# Seaquencer.net
KiCad netlist of a schematic drawn in EAGLE
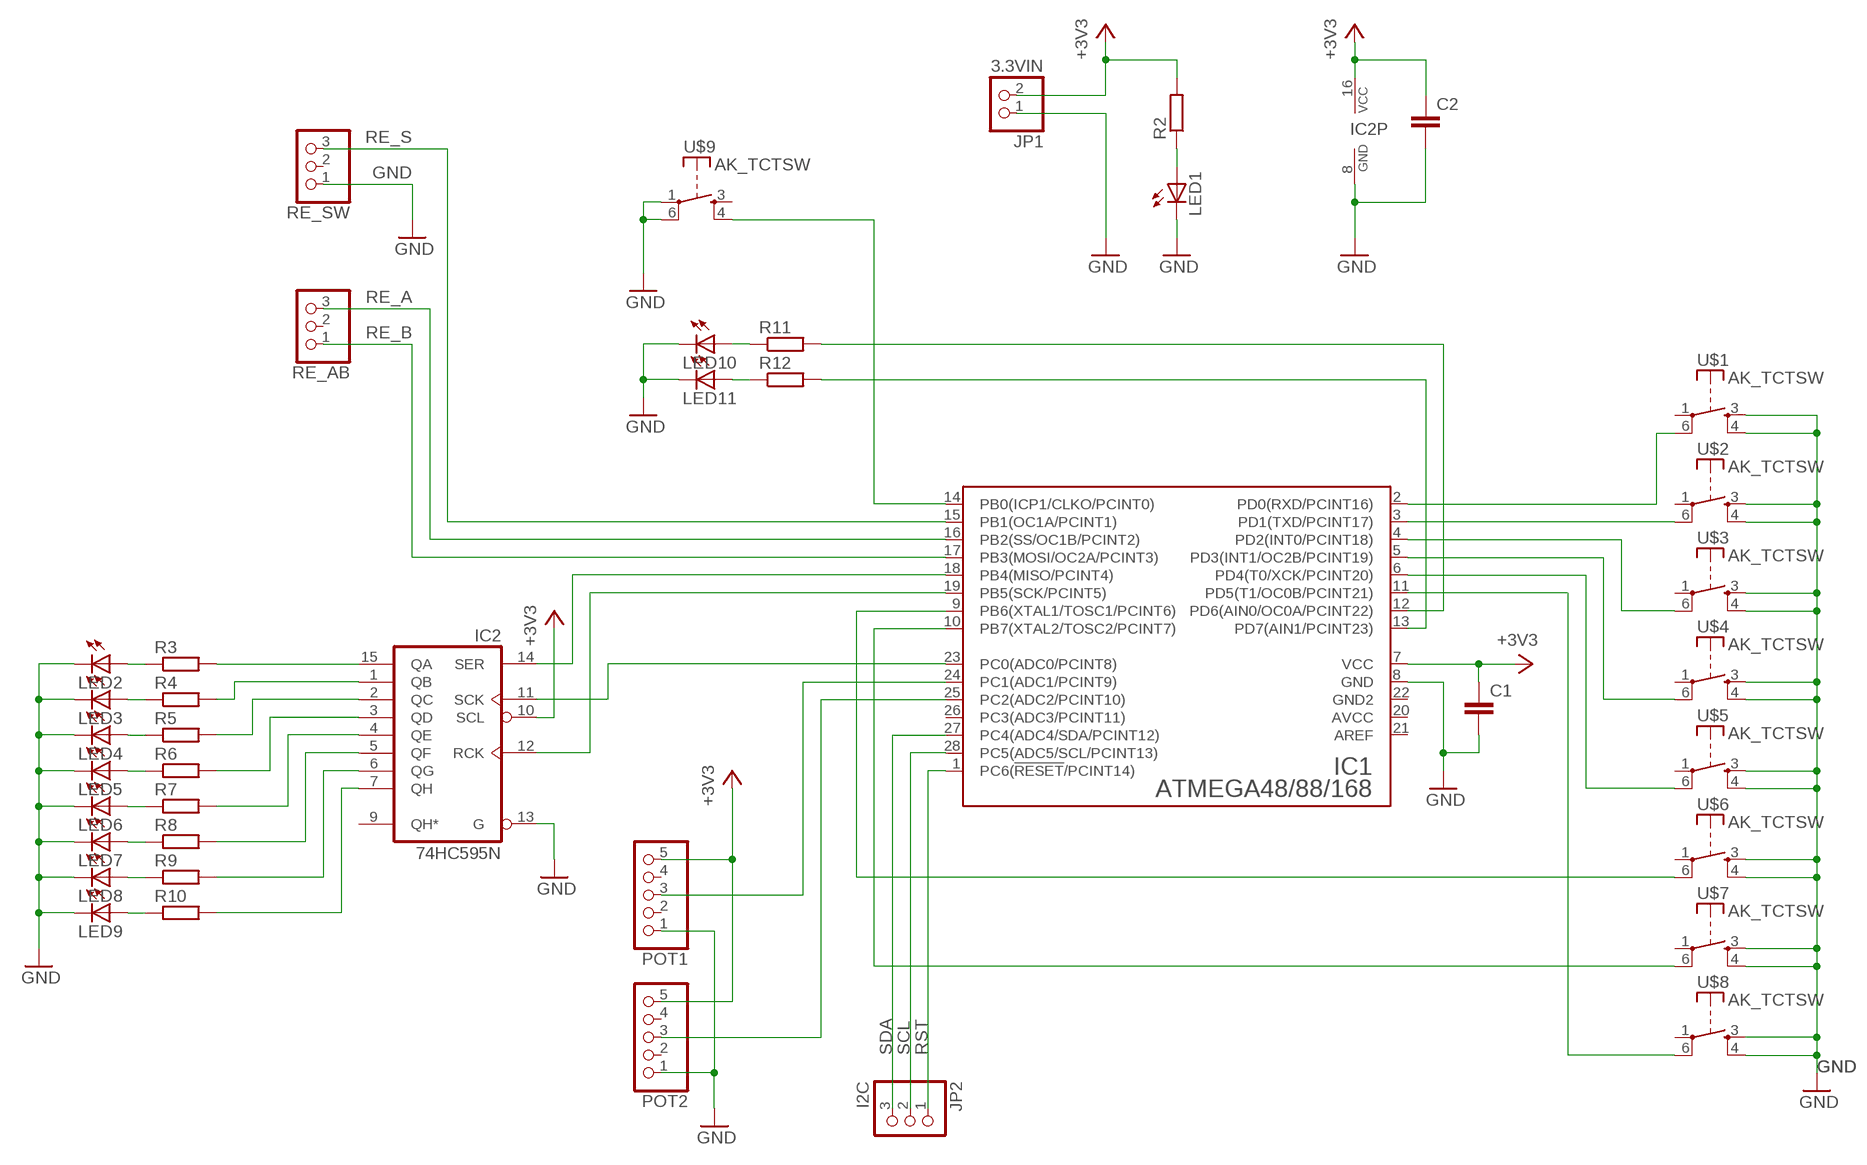
[diagram p0: schematic, sheet 1]

(export (version "E")
  (design (tool "Eeschema 10.0.6"))
  (components
    (comp (ref "C1")
      (value "C-EU025-024X044")
      (footprint "eagle-import:C025-024X044")
      (libsource (lib "eagle-import") (part "C-EU025-024X044"))
    )
    (comp (ref "C2")
      (value "C-EU025-024X044")
      (footprint "eagle-import:C025-024X044")
      (libsource (lib "eagle-import") (part "C-EU025-024X044"))
    )
    (comp (ref "IC1")
      (value "ATMEGA48/88/168")
      (footprint "eagle-import:DIL28-3")
      (libsource (lib "eagle-import") (part "ATMEGA48/88/168"))
    )
    (comp (ref "IC2")
      (value "74HC595N")
      (footprint "eagle-import:DIL16")
      (libsource (lib "eagle-import") (part "74595NHC"))
    )
    (comp (ref "JP1")
      (value "3.3VIN")
      (footprint "eagle-import:1X02")
      (libsource (lib "eagle-import") (part "PINHD-1X2"))
    )
    (comp (ref "JP2")
      (value "I2C")
      (footprint "eagle-import:1X03")
      (libsource (lib "eagle-import") (part "PINHD-1X3"))
    )
    (comp (ref "LED1")
      (value "LED3MM")
      (footprint "eagle-import:LED3MM")
      (libsource (lib "eagle-import") (part "LED3MM"))
    )
    (comp (ref "LED2")
      (value "LED3MM")
      (footprint "eagle-import:LED3MM")
      (libsource (lib "eagle-import") (part "LED3MM"))
    )
    (comp (ref "LED3")
      (value "LED3MM")
      (footprint "eagle-import:LED3MM")
      (libsource (lib "eagle-import") (part "LED3MM"))
    )
    (comp (ref "LED4")
      (value "LED3MM")
      (footprint "eagle-import:LED3MM")
      (libsource (lib "eagle-import") (part "LED3MM"))
    )
    (comp (ref "LED5")
      (value "LED3MM")
      (footprint "eagle-import:LED3MM")
      (libsource (lib "eagle-import") (part "LED3MM"))
    )
    (comp (ref "LED6")
      (value "LED3MM")
      (footprint "eagle-import:LED3MM")
      (libsource (lib "eagle-import") (part "LED3MM"))
    )
    (comp (ref "LED7")
      (value "LED3MM")
      (footprint "eagle-import:LED3MM")
      (libsource (lib "eagle-import") (part "LED3MM"))
    )
    (comp (ref "LED8")
      (value "LED3MM")
      (footprint "eagle-import:LED3MM")
      (libsource (lib "eagle-import") (part "LED3MM"))
    )
    (comp (ref "LED9")
      (value "LED3MM")
      (footprint "eagle-import:LED3MM")
      (libsource (lib "eagle-import") (part "LED3MM"))
    )
    (comp (ref "LED10")
      (value "LED3MM")
      (footprint "eagle-import:LED3MM")
      (libsource (lib "eagle-import") (part "LED3MM"))
    )
    (comp (ref "LED11")
      (value "LED3MM")
      (footprint "eagle-import:LED3MM")
      (libsource (lib "eagle-import") (part "LED3MM"))
    )
    (comp (ref "POT1")
      (value "PINHD-1X5")
      (footprint "eagle-import:1X05")
      (libsource (lib "eagle-import") (part "PINHD-1X5"))
    )
    (comp (ref "POT2")
      (value "PINHD-1X5")
      (footprint "eagle-import:1X05")
      (libsource (lib "eagle-import") (part "PINHD-1X5"))
    )
    (comp (ref "R2")
      (value "R-EU_0207/7")
      (footprint "eagle-import:0207_7")
      (libsource (lib "eagle-import") (part "R-EU_0207/7"))
    )
    (comp (ref "R3")
      (value "R-EU_0207/7")
      (footprint "eagle-import:0207_7")
      (libsource (lib "eagle-import") (part "R-EU_0207/7"))
    )
    (comp (ref "R4")
      (value "R-EU_0207/7")
      (footprint "eagle-import:0207_7")
      (libsource (lib "eagle-import") (part "R-EU_0207/7"))
    )
    (comp (ref "R5")
      (value "R-EU_0207/7")
      (footprint "eagle-import:0207_7")
      (libsource (lib "eagle-import") (part "R-EU_0207/7"))
    )
    (comp (ref "R6")
      (value "R-EU_0207/7")
      (footprint "eagle-import:0207_7")
      (libsource (lib "eagle-import") (part "R-EU_0207/7"))
    )
    (comp (ref "R7")
      (value "R-EU_0207/7")
      (footprint "eagle-import:0207_7")
      (libsource (lib "eagle-import") (part "R-EU_0207/7"))
    )
    (comp (ref "R8")
      (value "R-EU_0207/7")
      (footprint "eagle-import:0207_7")
      (libsource (lib "eagle-import") (part "R-EU_0207/7"))
    )
    (comp (ref "R9")
      (value "R-EU_0207/7")
      (footprint "eagle-import:0207_7")
      (libsource (lib "eagle-import") (part "R-EU_0207/7"))
    )
    (comp (ref "R10")
      (value "R-EU_0207/7")
      (footprint "eagle-import:0207_7")
      (libsource (lib "eagle-import") (part "R-EU_0207/7"))
    )
    (comp (ref "R11")
      (value "R-EU_0207/7")
      (footprint "eagle-import:0207_7")
      (libsource (lib "eagle-import") (part "R-EU_0207/7"))
    )
    (comp (ref "R12")
      (value "R-EU_0207/7")
      (footprint "eagle-import:0207_7")
      (libsource (lib "eagle-import") (part "R-EU_0207/7"))
    )
    (comp (ref "RE_AB")
      (value "PINHD-1X3")
      (footprint "eagle-import:1X03")
      (libsource (lib "eagle-import") (part "PINHD-1X3"))
    )
    (comp (ref "RE_SW")
      (value "PINHD-1X3")
      (footprint "eagle-import:1X03")
      (libsource (lib "eagle-import") (part "PINHD-1X3"))
    )
    (comp (ref "U$1")
      (value "AK_TCTSW")
      (footprint "eagle-import:TME1")
      (libsource (lib "eagle-import") (part "AK_TCTSW"))
    )
    (comp (ref "U$2")
      (value "AK_TCTSW")
      (footprint "eagle-import:TME1")
      (libsource (lib "eagle-import") (part "AK_TCTSW"))
    )
    (comp (ref "U$3")
      (value "AK_TCTSW")
      (footprint "eagle-import:TME1")
      (libsource (lib "eagle-import") (part "AK_TCTSW"))
    )
    (comp (ref "U$4")
      (value "AK_TCTSW")
      (footprint "eagle-import:TME1")
      (libsource (lib "eagle-import") (part "AK_TCTSW"))
    )
    (comp (ref "U$5")
      (value "AK_TCTSW")
      (footprint "eagle-import:TME1")
      (libsource (lib "eagle-import") (part "AK_TCTSW"))
    )
    (comp (ref "U$6")
      (value "AK_TCTSW")
      (footprint "eagle-import:TME1")
      (libsource (lib "eagle-import") (part "AK_TCTSW"))
    )
    (comp (ref "U$7")
      (value "AK_TCTSW")
      (footprint "eagle-import:TME1")
      (libsource (lib "eagle-import") (part "AK_TCTSW"))
    )
    (comp (ref "U$8")
      (value "AK_TCTSW")
      (footprint "eagle-import:TME1")
      (libsource (lib "eagle-import") (part "AK_TCTSW"))
    )
    (comp (ref "U$9")
      (value "AK_TCTSW")
      (footprint "eagle-import:TME1")
      (libsource (lib "eagle-import") (part "AK_TCTSW"))
    )
  )
  (nets
    (net (code "1") (name "+3V3") (class "Default")
      (node (ref "C1") (pin "1") (pinfunction "1_1") (pintype "passive"))
      (node (ref "C2") (pin "1") (pinfunction "1_1") (pintype "passive"))
      (node (ref "IC1") (pin "7") (pinfunction "VCC_7") (pintype "power_in"))
      (node (ref "IC2") (pin "10") (pinfunction "SCL_10") (pintype "input"))
      (node (ref "IC2") (pin "16") (pinfunction "VCC_16") (pintype "power_in"))
      (node (ref "JP1") (pin "2") (pinfunction "2_2") (pintype "passive"))
      (node (ref "POT1") (pin "5") (pinfunction "5_5") (pintype "passive"))
      (node (ref "POT2") (pin "5") (pinfunction "5_5") (pintype "passive"))
      (node (ref "R2") (pin "2") (pinfunction "2_2") (pintype "passive"))
    )
    (net (code "2") (name "/AVCC") (class "Default")
      (node (ref "IC1") (pin "20") (pinfunction "AVCC_20") (pintype "power_in"))
    )
    (net (code "3") (name "/GND2") (class "Default")
      (node (ref "IC1") (pin "22") (pinfunction "GND2_22") (pintype "power_in"))
    )
    (net (code "4") (name "/RE_A") (class "Default")
      (node (ref "IC1") (pin "16") (pinfunction "PB2(SS/OC1B/PCINT2)_16") (pintype "bidirectional"))
      (node (ref "RE_AB") (pin "3") (pinfunction "3_3") (pintype "passive"))
    )
    (net (code "5") (name "/RE_B") (class "Default")
      (node (ref "IC1") (pin "17") (pinfunction "PB3(MOSI/OC2A/PCINT3)_17") (pintype "bidirectional"))
      (node (ref "RE_AB") (pin "1") (pinfunction "1_1") (pintype "passive"))
    )
    (net (code "6") (name "/RE_S") (class "Default")
      (node (ref "IC1") (pin "15") (pinfunction "PB1(OC1A/PCINT1)_15") (pintype "bidirectional"))
      (node (ref "RE_SW") (pin "3") (pinfunction "3_3") (pintype "passive"))
    )
    (net (code "7") (name "/RST") (class "Default")
      (node (ref "IC1") (pin "1") (pinfunction "PC6(~{RESET}/PCINT14)_1") (pintype "bidirectional"))
      (node (ref "JP2") (pin "1") (pinfunction "1_1") (pintype "passive"))
    )
    (net (code "8") (name "/SCL") (class "Default")
      (node (ref "IC1") (pin "28") (pinfunction "PC5(ADC5/SCL/PCINT13)_28") (pintype "bidirectional"))
      (node (ref "JP2") (pin "2") (pinfunction "2_2") (pintype "passive"))
    )
    (net (code "9") (name "/SDA") (class "Default")
      (node (ref "IC1") (pin "27") (pinfunction "PC4(ADC4/SDA/PCINT12)_27") (pintype "bidirectional"))
      (node (ref "JP2") (pin "3") (pinfunction "3_3") (pintype "passive"))
    )
    (net (code "10") (name "GND") (class "Default")
      (node (ref "C1") (pin "2") (pinfunction "2_2") (pintype "passive"))
      (node (ref "C2") (pin "2") (pinfunction "2_2") (pintype "passive"))
      (node (ref "IC1") (pin "8") (pinfunction "GND_8") (pintype "power_in"))
      (node (ref "IC2") (pin "13") (pinfunction "G_13") (pintype "input"))
      (node (ref "IC2") (pin "8") (pinfunction "GND_8") (pintype "power_in"))
      (node (ref "JP1") (pin "1") (pinfunction "1_1") (pintype "passive"))
      (node (ref "LED1") (pin "K") (pinfunction "C_K") (pintype "passive"))
      (node (ref "LED10") (pin "K") (pinfunction "C_K") (pintype "passive"))
      (node (ref "LED11") (pin "K") (pinfunction "C_K") (pintype "passive"))
      (node (ref "LED2") (pin "K") (pinfunction "C_K") (pintype "passive"))
      (node (ref "LED3") (pin "K") (pinfunction "C_K") (pintype "passive"))
      (node (ref "LED4") (pin "K") (pinfunction "C_K") (pintype "passive"))
      (node (ref "LED5") (pin "K") (pinfunction "C_K") (pintype "passive"))
      (node (ref "LED6") (pin "K") (pinfunction "C_K") (pintype "passive"))
      (node (ref "LED7") (pin "K") (pinfunction "C_K") (pintype "passive"))
      (node (ref "LED8") (pin "K") (pinfunction "C_K") (pintype "passive"))
      (node (ref "LED9") (pin "K") (pinfunction "C_K") (pintype "passive"))
      (node (ref "POT1") (pin "1") (pinfunction "1_1") (pintype "passive"))
      (node (ref "POT2") (pin "1") (pinfunction "1_1") (pintype "passive"))
      (node (ref "RE_SW") (pin "1") (pinfunction "1_1") (pintype "passive"))
      (node (ref "U$1") (pin "3") (pinfunction "S_3") (pintype "passive"))
      (node (ref "U$1") (pin "4") (pinfunction "S_4") (pintype "passive"))
      (node (ref "U$2") (pin "3") (pinfunction "S_3") (pintype "passive"))
      (node (ref "U$2") (pin "4") (pinfunction "S_4") (pintype "passive"))
      (node (ref "U$3") (pin "3") (pinfunction "S_3") (pintype "passive"))
      (node (ref "U$3") (pin "4") (pinfunction "S_4") (pintype "passive"))
      (node (ref "U$4") (pin "3") (pinfunction "S_3") (pintype "passive"))
      (node (ref "U$4") (pin "4") (pinfunction "S_4") (pintype "passive"))
      (node (ref "U$5") (pin "3") (pinfunction "S_3") (pintype "passive"))
      (node (ref "U$5") (pin "4") (pinfunction "S_4") (pintype "passive"))
      (node (ref "U$6") (pin "3") (pinfunction "S_3") (pintype "passive"))
      (node (ref "U$6") (pin "4") (pinfunction "S_4") (pintype "passive"))
      (node (ref "U$7") (pin "3") (pinfunction "S_3") (pintype "passive"))
      (node (ref "U$7") (pin "4") (pinfunction "S_4") (pintype "passive"))
      (node (ref "U$8") (pin "3") (pinfunction "S_3") (pintype "passive"))
      (node (ref "U$8") (pin "4") (pinfunction "S_4") (pintype "passive"))
      (node (ref "U$9") (pin "1") (pinfunction "P_1") (pintype "passive"))
      (node (ref "U$9") (pin "6") (pinfunction "P_6") (pintype "passive"))
    )
    (net (code "11") (name "Net-(IC1-PB0(ICP1{slash}CLKO{slash}PCINT0))") (class "Default")
      (node (ref "IC1") (pin "14") (pinfunction "PB0(ICP1/CLKO/PCINT0)_14") (pintype "bidirectional"))
      (node (ref "U$9") (pin "4") (pinfunction "S_4") (pintype "passive"))
    )
    (net (code "12") (name "Net-(IC1-PB4(MISO{slash}PCINT4))") (class "Default")
      (node (ref "IC1") (pin "18") (pinfunction "PB4(MISO/PCINT4)_18") (pintype "bidirectional"))
      (node (ref "IC2") (pin "14") (pinfunction "SER_14") (pintype "input"))
    )
    (net (code "13") (name "Net-(IC1-PB5(SCK{slash}PCINT5))") (class "Default")
      (node (ref "IC1") (pin "19") (pinfunction "PB5(SCK/PCINT5)_19") (pintype "bidirectional"))
      (node (ref "IC2") (pin "12") (pinfunction "RCK_12") (pintype "input"))
    )
    (net (code "14") (name "Net-(IC1-PB6(XTAL1{slash}TOSC1{slash}PCINT6))") (class "Default")
      (node (ref "IC1") (pin "9") (pinfunction "PB6(XTAL1/TOSC1/PCINT6)_9") (pintype "bidirectional"))
      (node (ref "U$6") (pin "6") (pinfunction "P_6") (pintype "passive"))
    )
    (net (code "15") (name "Net-(IC1-PB7(XTAL2{slash}TOSC2{slash}PCINT7))") (class "Default")
      (node (ref "IC1") (pin "10") (pinfunction "PB7(XTAL2/TOSC2/PCINT7)_10") (pintype "bidirectional"))
      (node (ref "U$7") (pin "6") (pinfunction "P_6") (pintype "passive"))
    )
    (net (code "16") (name "Net-(IC1-PC0(ADC0{slash}PCINT8))") (class "Default")
      (node (ref "IC1") (pin "23") (pinfunction "PC0(ADC0/PCINT8)_23") (pintype "bidirectional"))
      (node (ref "IC2") (pin "11") (pinfunction "SCK_11") (pintype "input"))
    )
    (net (code "17") (name "Net-(IC1-PC1(ADC1{slash}PCINT9))") (class "Default")
      (node (ref "IC1") (pin "24") (pinfunction "PC1(ADC1/PCINT9)_24") (pintype "bidirectional"))
      (node (ref "POT1") (pin "3") (pinfunction "3_3") (pintype "passive"))
    )
    (net (code "18") (name "Net-(IC1-PC2(ADC2{slash}PCINT10))") (class "Default")
      (node (ref "IC1") (pin "25") (pinfunction "PC2(ADC2/PCINT10)_25") (pintype "bidirectional"))
      (node (ref "POT2") (pin "3") (pinfunction "3_3") (pintype "passive"))
    )
    (net (code "19") (name "Net-(IC1-PD0(RXD{slash}PCINT16))") (class "Default")
      (node (ref "IC1") (pin "2") (pinfunction "PD0(RXD/PCINT16)_2") (pintype "bidirectional"))
      (node (ref "U$1") (pin "6") (pinfunction "P_6") (pintype "passive"))
    )
    (net (code "20") (name "Net-(IC1-PD1(TXD{slash}PCINT17))") (class "Default")
      (node (ref "IC1") (pin "3") (pinfunction "PD1(TXD/PCINT17)_3") (pintype "bidirectional"))
      (node (ref "U$2") (pin "6") (pinfunction "P_6") (pintype "passive"))
    )
    (net (code "21") (name "Net-(IC1-PD2(INT0{slash}PCINT18))") (class "Default")
      (node (ref "IC1") (pin "4") (pinfunction "PD2(INT0/PCINT18)_4") (pintype "bidirectional"))
      (node (ref "U$3") (pin "6") (pinfunction "P_6") (pintype "passive"))
    )
    (net (code "22") (name "Net-(IC1-PD3(INT1{slash}OC2B{slash}PCINT19))") (class "Default")
      (node (ref "IC1") (pin "5") (pinfunction "PD3(INT1/OC2B/PCINT19)_5") (pintype "bidirectional"))
      (node (ref "U$4") (pin "6") (pinfunction "P_6") (pintype "passive"))
    )
    (net (code "23") (name "Net-(IC1-PD4(T0{slash}XCK{slash}PCINT20))") (class "Default")
      (node (ref "IC1") (pin "6") (pinfunction "PD4(T0/XCK/PCINT20)_6") (pintype "bidirectional"))
      (node (ref "U$5") (pin "6") (pinfunction "P_6") (pintype "passive"))
    )
    (net (code "24") (name "Net-(IC1-PD5(T1{slash}OC0B{slash}PCINT21))") (class "Default")
      (node (ref "IC1") (pin "11") (pinfunction "PD5(T1/OC0B/PCINT21)_11") (pintype "bidirectional"))
      (node (ref "U$8") (pin "6") (pinfunction "P_6") (pintype "passive"))
    )
    (net (code "25") (name "Net-(IC1-PD6(AIN0{slash}OC0A{slash}PCINT22))") (class "Default")
      (node (ref "IC1") (pin "12") (pinfunction "PD6(AIN0/OC0A/PCINT22)_12") (pintype "bidirectional"))
      (node (ref "R11") (pin "2") (pinfunction "2_2") (pintype "passive"))
    )
    (net (code "26") (name "Net-(IC1-PD7(AIN1{slash}PCINT23))") (class "Default")
      (node (ref "IC1") (pin "13") (pinfunction "PD7(AIN1/PCINT23)_13") (pintype "bidirectional"))
      (node (ref "R12") (pin "2") (pinfunction "2_2") (pintype "passive"))
    )
    (net (code "27") (name "Net-(IC2A-QA)") (class "Default")
      (node (ref "IC2") (pin "15") (pinfunction "QA_15") (pintype "tri_state"))
      (node (ref "R3") (pin "2") (pinfunction "2_2") (pintype "passive"))
    )
    (net (code "28") (name "Net-(IC2A-QB)") (class "Default")
      (node (ref "IC2") (pin "1") (pinfunction "QB_1") (pintype "tri_state"))
      (node (ref "R4") (pin "2") (pinfunction "2_2") (pintype "passive"))
    )
    (net (code "29") (name "Net-(IC2A-QC)") (class "Default")
      (node (ref "IC2") (pin "2") (pinfunction "QC_2") (pintype "tri_state"))
      (node (ref "R5") (pin "2") (pinfunction "2_2") (pintype "passive"))
    )
    (net (code "30") (name "Net-(IC2A-QD)") (class "Default")
      (node (ref "IC2") (pin "3") (pinfunction "QD_3") (pintype "tri_state"))
      (node (ref "R6") (pin "2") (pinfunction "2_2") (pintype "passive"))
    )
    (net (code "31") (name "Net-(IC2A-QE)") (class "Default")
      (node (ref "IC2") (pin "4") (pinfunction "QE_4") (pintype "tri_state"))
      (node (ref "R7") (pin "2") (pinfunction "2_2") (pintype "passive"))
    )
    (net (code "32") (name "Net-(IC2A-QF)") (class "Default")
      (node (ref "IC2") (pin "5") (pinfunction "QF_5") (pintype "tri_state"))
      (node (ref "R8") (pin "2") (pinfunction "2_2") (pintype "passive"))
    )
    (net (code "33") (name "Net-(IC2A-QG)") (class "Default")
      (node (ref "IC2") (pin "6") (pinfunction "QG_6") (pintype "tri_state"))
      (node (ref "R9") (pin "2") (pinfunction "2_2") (pintype "passive"))
    )
    (net (code "34") (name "Net-(IC2A-QH)") (class "Default")
      (node (ref "IC2") (pin "7") (pinfunction "QH_7") (pintype "tri_state"))
      (node (ref "R10") (pin "2") (pinfunction "2_2") (pintype "passive"))
    )
    (net (code "35") (name "Net-(LED1-PadA)") (class "Default")
      (node (ref "LED1") (pin "A") (pinfunction "A_A") (pintype "passive"))
      (node (ref "R2") (pin "1") (pinfunction "1_1") (pintype "passive"))
    )
    (net (code "36") (name "Net-(LED2-PadA)") (class "Default")
      (node (ref "LED2") (pin "A") (pinfunction "A_A") (pintype "passive"))
      (node (ref "R3") (pin "1") (pinfunction "1_1") (pintype "passive"))
    )
    (net (code "37") (name "Net-(LED3-PadA)") (class "Default")
      (node (ref "LED3") (pin "A") (pinfunction "A_A") (pintype "passive"))
      (node (ref "R4") (pin "1") (pinfunction "1_1") (pintype "passive"))
    )
    (net (code "38") (name "Net-(LED4-PadA)") (class "Default")
      (node (ref "LED4") (pin "A") (pinfunction "A_A") (pintype "passive"))
      (node (ref "R5") (pin "1") (pinfunction "1_1") (pintype "passive"))
    )
    (net (code "39") (name "Net-(LED5-PadA)") (class "Default")
      (node (ref "LED5") (pin "A") (pinfunction "A_A") (pintype "passive"))
      (node (ref "R6") (pin "1") (pinfunction "1_1") (pintype "passive"))
    )
    (net (code "40") (name "Net-(LED6-PadA)") (class "Default")
      (node (ref "LED6") (pin "A") (pinfunction "A_A") (pintype "passive"))
      (node (ref "R7") (pin "1") (pinfunction "1_1") (pintype "passive"))
    )
    (net (code "41") (name "Net-(LED7-PadA)") (class "Default")
      (node (ref "LED7") (pin "A") (pinfunction "A_A") (pintype "passive"))
      (node (ref "R8") (pin "1") (pinfunction "1_1") (pintype "passive"))
    )
    (net (code "42") (name "Net-(LED8-PadA)") (class "Default")
      (node (ref "LED8") (pin "A") (pinfunction "A_A") (pintype "passive"))
      (node (ref "R9") (pin "1") (pinfunction "1_1") (pintype "passive"))
    )
    (net (code "43") (name "Net-(LED9-PadA)") (class "Default")
      (node (ref "LED9") (pin "A") (pinfunction "A_A") (pintype "passive"))
      (node (ref "R10") (pin "1") (pinfunction "1_1") (pintype "passive"))
    )
    (net (code "44") (name "Net-(LED10-PadA)") (class "Default")
      (node (ref "LED10") (pin "A") (pinfunction "A_A") (pintype "passive"))
      (node (ref "R11") (pin "1") (pinfunction "1_1") (pintype "passive"))
    )
    (net (code "45") (name "Net-(LED11-PadA)") (class "Default")
      (node (ref "LED11") (pin "A") (pinfunction "A_A") (pintype "passive"))
      (node (ref "R12") (pin "1") (pinfunction "1_1") (pintype "passive"))
    )
    (net (code "46") (name "unconnected-(IC1-AREF-Pad21)") (class "Default")
      (node (ref "IC1") (pin "21") (pinfunction "AREF_21") (pintype "passive"))
    )
    (net (code "47") (name "unconnected-(IC1-PC3(ADC3{slash}PCINT11)-Pad26)") (class "Default")
      (node (ref "IC1") (pin "26") (pinfunction "PC3(ADC3/PCINT11)_26") (pintype "bidirectional"))
    )
    (net (code "48") (name "unconnected-(IC2A-QH*-Pad9)") (class "Default")
      (node (ref "IC2") (pin "9") (pinfunction "QH*_9") (pintype "tri_state"))
    )
    (net (code "49") (name "unconnected-(POT1-Pad2)") (class "Default")
      (node (ref "POT1") (pin "2") (pinfunction "2_2") (pintype "passive"))
    )
    (net (code "50") (name "unconnected-(POT1-Pad4)") (class "Default")
      (node (ref "POT1") (pin "4") (pinfunction "4_4") (pintype "passive"))
    )
    (net (code "51") (name "unconnected-(POT2-Pad2)") (class "Default")
      (node (ref "POT2") (pin "2") (pinfunction "2_2") (pintype "passive"))
    )
    (net (code "52") (name "unconnected-(POT2-Pad4)") (class "Default")
      (node (ref "POT2") (pin "4") (pinfunction "4_4") (pintype "passive"))
    )
    (net (code "53") (name "unconnected-(RE_AB-Pad2)") (class "Default")
      (node (ref "RE_AB") (pin "2") (pinfunction "2_2") (pintype "passive"))
    )
    (net (code "54") (name "unconnected-(RE_SW-Pad2)") (class "Default")
      (node (ref "RE_SW") (pin "2") (pinfunction "2_2") (pintype "passive"))
    )
    (net (code "55") (name "unconnected-(U$1-P-Pad1)") (class "Default")
      (node (ref "U$1") (pin "1") (pinfunction "P_1") (pintype "passive"))
    )
    (net (code "56") (name "unconnected-(U$2-P-Pad1)") (class "Default")
      (node (ref "U$2") (pin "1") (pinfunction "P_1") (pintype "passive"))
    )
    (net (code "57") (name "unconnected-(U$3-P-Pad1)") (class "Default")
      (node (ref "U$3") (pin "1") (pinfunction "P_1") (pintype "passive"))
    )
    (net (code "58") (name "unconnected-(U$4-P-Pad1)") (class "Default")
      (node (ref "U$4") (pin "1") (pinfunction "P_1") (pintype "passive"))
    )
    (net (code "59") (name "unconnected-(U$5-P-Pad1)") (class "Default")
      (node (ref "U$5") (pin "1") (pinfunction "P_1") (pintype "passive"))
    )
    (net (code "60") (name "unconnected-(U$6-P-Pad1)") (class "Default")
      (node (ref "U$6") (pin "1") (pinfunction "P_1") (pintype "passive"))
    )
    (net (code "61") (name "unconnected-(U$7-P-Pad1)") (class "Default")
      (node (ref "U$7") (pin "1") (pinfunction "P_1") (pintype "passive"))
    )
    (net (code "62") (name "unconnected-(U$8-P-Pad1)") (class "Default")
      (node (ref "U$8") (pin "1") (pinfunction "P_1") (pintype "passive"))
    )
    (net (code "63") (name "unconnected-(U$9-S-Pad3)") (class "Default")
      (node (ref "U$9") (pin "3") (pinfunction "S_3") (pintype "passive"))
    )
  )
)
